# 04_WIFI_BLE_ANTENNA.net
KiCad netlist of a schematic drawn in Altium Designer
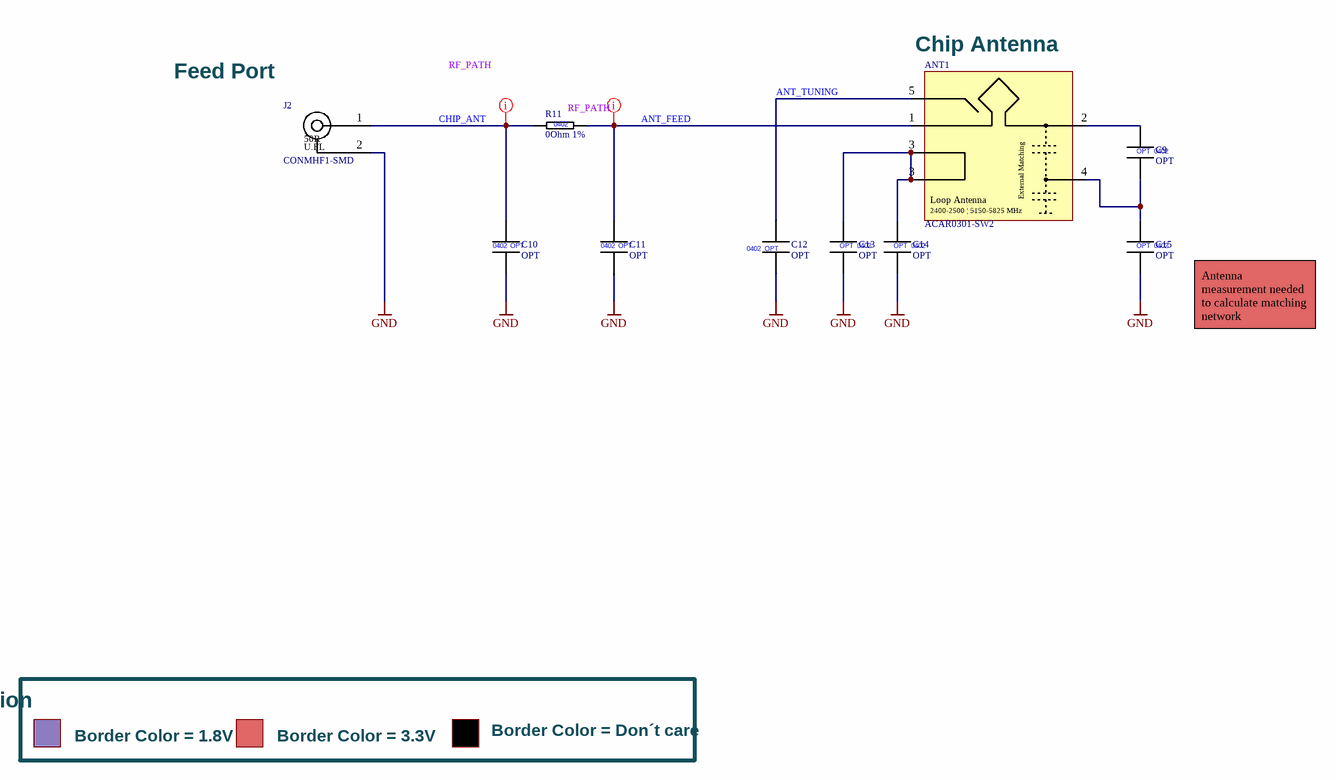
[diagram p0: 04_WIFI_BLE_ANTENNA.SchDoc]

(export (version "E")
  (design (tool "Eeschema 10.0.6"))
  (components
    (comp (ref "ANT1")
      (value "ACAR0301-SW2")
      (footprint "QV_Antenna:ANTENNA_ACAR0301-SW2_FEED_LEFT")
      (description "Ceramic Chip Antenna ACAR0301-SW2 2.4 - 5.825GHZ")
      (libsource (lib "QV_Antenna") (part "Chip Antenna_ACAR0301-SW2"))
    )
    (comp (ref "C9")
      (value "OPT")
      (footprint "QV_Cap:CAPC1005X06L")
      (description "Optional Capacitor 0402")
      (libsource (lib "") (part "CAP_0402_OPT_1"))
    )
    (comp (ref "C10")
      (value "OPT")
      (footprint "QV_Cap:CAPC1005X06L")
      (description "Optional Capacitor 0402")
      (libsource (lib "") (part "CAP_0402_OPT_1"))
    )
    (comp (ref "C11")
      (value "OPT")
      (footprint "QV_Cap:CAPC1005X06L")
      (description "Optional Capacitor 0402")
      (libsource (lib "") (part "CAP_0402_OPT_1"))
    )
    (comp (ref "C12")
      (value "OPT")
      (footprint "QV_Cap:CAPC1005X06L")
      (description "Optional Capacitor 0402")
      (libsource (lib "QV_Cap") (part "CAP_0402_OPT"))
    )
    (comp (ref "C13")
      (value "OPT")
      (footprint "QV_Cap:CAPC1005X06L")
      (description "Optional Capacitor 0402")
      (libsource (lib "") (part "CAP_0402_OPT_1"))
    )
    (comp (ref "C14")
      (value "OPT")
      (footprint "QV_Cap:CAPC1005X06L")
      (description "Optional Capacitor 0402")
      (libsource (lib "") (part "CAP_0402_OPT_1"))
    )
    (comp (ref "C15")
      (value "OPT")
      (footprint "QV_Cap:CAPC1005X06L")
      (description "Optional Capacitor 0402")
      (libsource (lib "") (part "CAP_0402_OPT_1"))
    )
    (comp (ref "J2")
      (value "CONMHF1-SMD")
      (footprint "QV_Con:U.FL Jack SMD")
      (description "U.FL Type Jack PCB SMD RF Connector")
      (libsource (lib "QV_Con") (part "U.FL_CONMHF1-SMD"))
    )
    (comp (ref "R11")
      (value "0Ohm 1%")
      (footprint "QV_Res:RESC1005X04L")
      (description "Thick Film Resistors - SMD 0OHM 1%")
      (libsource (lib "QV_res") (part "RES_0402_0R_1%"))
    )
  )
  (nets
    (net (code "1") (name "/ANT_FEED") (class "Default")
      (node (ref "ANT1") (pin "1") (pinfunction "1_1") (pintype "passive"))
      (node (ref "C11") (pin "1") (pinfunction "1_1") (pintype "passive"))
      (node (ref "R11") (pin "2") (pinfunction "2_2") (pintype "passive"))
    )
    (net (code "2") (name "/ANT_TUNING") (class "Default")
      (node (ref "ANT1") (pin "5") (pinfunction "5_5") (pintype "passive"))
      (node (ref "C12") (pin "2") (pinfunction "2_2") (pintype "passive"))
    )
    (net (code "3") (name "/CHIP_ANT") (class "Default")
      (node (ref "C10") (pin "1") (pinfunction "1_1") (pintype "passive"))
      (node (ref "J2") (pin "1") (pinfunction "1_1") (pintype "passive"))
      (node (ref "R11") (pin "1") (pinfunction "1_1") (pintype "passive"))
    )
    (net (code "4") (name "GND") (class "Default")
      (node (ref "C10") (pin "2") (pinfunction "2_2") (pintype "passive"))
      (node (ref "C11") (pin "2") (pinfunction "2_2") (pintype "passive"))
      (node (ref "C12") (pin "1") (pinfunction "1_1") (pintype "passive"))
      (node (ref "C13") (pin "2") (pinfunction "2_2") (pintype "passive"))
      (node (ref "C14") (pin "2") (pinfunction "2_2") (pintype "passive"))
      (node (ref "C15") (pin "2") (pinfunction "2_2") (pintype "passive"))
      (node (ref "J2") (pin "2") (pinfunction "2_2") (pintype "passive"))
    )
    (net (code "5") (name "Net-(ANT1-Pad2)") (class "Default")
      (node (ref "ANT1") (pin "2") (pinfunction "2_2") (pintype "passive"))
      (node (ref "C9") (pin "1") (pinfunction "1_1") (pintype "passive"))
    )
    (net (code "6") (name "Net-(ANT1-Pad3)") (class "Default")
      (node (ref "ANT1") (pin "3") (pinfunction "3_3") (pintype "passive"))
      (node (ref "C13") (pin "1") (pinfunction "1_1") (pintype "passive"))
      (node (ref "C14") (pin "1") (pinfunction "1_1") (pintype "passive"))
    )
    (net (code "7") (name "Net-(ANT1-Pad4)") (class "Default")
      (node (ref "ANT1") (pin "4") (pinfunction "4_4") (pintype "passive"))
      (node (ref "C15") (pin "1") (pinfunction "1_1") (pintype "passive"))
      (node (ref "C9") (pin "2") (pinfunction "2_2") (pintype "passive"))
    )
  )
)
